# SpiderBackBackup.net
KiCad netlist of a schematic drawn in EAGLE
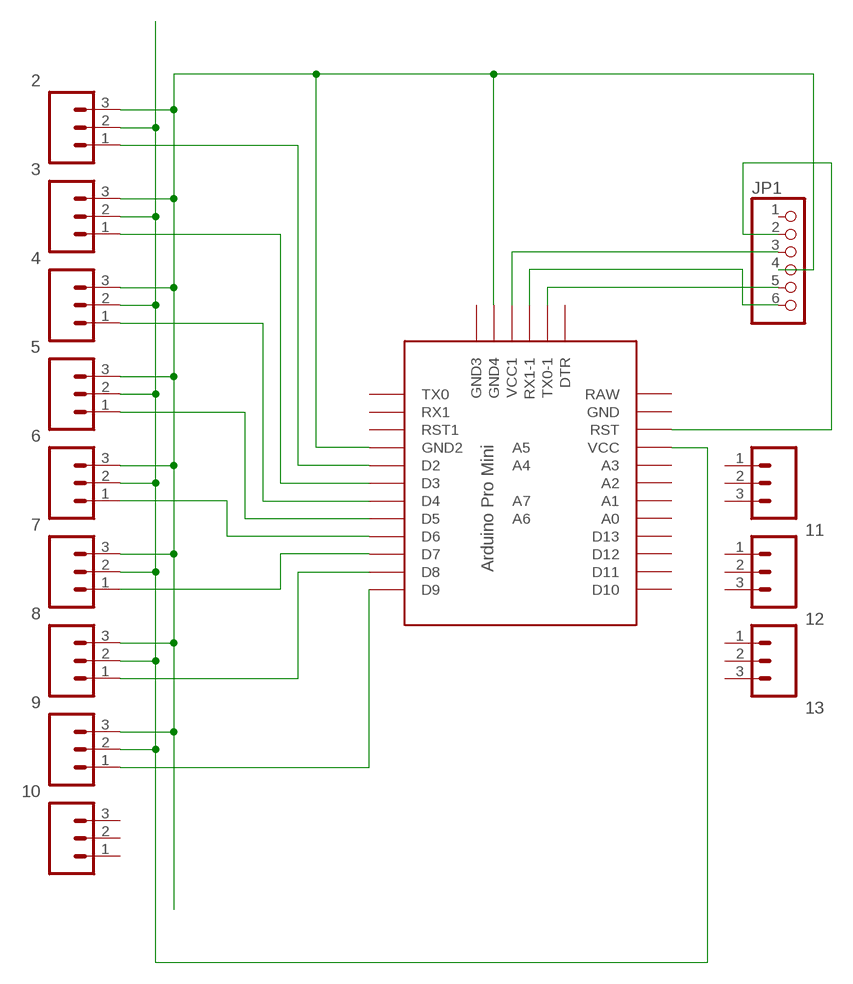
[diagram p0: schematic, sheet 1]

(export (version "E")
  (design (tool "Eeschema 10.0.6"))
  (components
    (comp (ref "2")
      (value "M03PTH")
      (footprint "eagle-import:1X03")
      (libsource (lib "eagle-import") (part "M03PTH"))
    )
    (comp (ref "3")
      (value "M03PTH")
      (footprint "eagle-import:1X03")
      (libsource (lib "eagle-import") (part "M03PTH"))
    )
    (comp (ref "4")
      (value "M03PTH")
      (footprint "eagle-import:1X03")
      (libsource (lib "eagle-import") (part "M03PTH"))
    )
    (comp (ref "5")
      (value "M03PTH")
      (footprint "eagle-import:1X03")
      (libsource (lib "eagle-import") (part "M03PTH"))
    )
    (comp (ref "6")
      (value "M03PTH")
      (footprint "eagle-import:1X03")
      (libsource (lib "eagle-import") (part "M03PTH"))
    )
    (comp (ref "7")
      (value "M03PTH")
      (footprint "eagle-import:1X03")
      (libsource (lib "eagle-import") (part "M03PTH"))
    )
    (comp (ref "8")
      (value "M03PTH")
      (footprint "eagle-import:1X03")
      (libsource (lib "eagle-import") (part "M03PTH"))
    )
    (comp (ref "9")
      (value "M03PTH")
      (footprint "eagle-import:1X03")
      (libsource (lib "eagle-import") (part "M03PTH"))
    )
    (comp (ref "10")
      (value "M03PTH")
      (footprint "eagle-import:1X03")
      (libsource (lib "eagle-import") (part "M03PTH"))
    )
    (comp (ref "11")
      (value "M03PTH")
      (footprint "eagle-import:1X03")
      (libsource (lib "eagle-import") (part "M03PTH"))
    )
    (comp (ref "12")
      (value "M03PTH")
      (footprint "eagle-import:1X03")
      (libsource (lib "eagle-import") (part "M03PTH"))
    )
    (comp (ref "13")
      (value "M03PTH")
      (footprint "eagle-import:1X03")
      (libsource (lib "eagle-import") (part "M03PTH"))
    )
    (comp (ref "JP1")
      (value "PINHD-1X6CB")
      (footprint "eagle-import:1X06-CLEANBIG")
      (libsource (lib "eagle-import") (part "PINHD-1X6CB"))
    )
    (comp (ref "U$1")
      (value "PRO-MINI-2")
      (footprint "eagle-import:PRO-MINI-2")
      (libsource (lib "eagle-import") (part "PRO-MINI-2"))
    )
  )
  (nets
    (net (code "1") (name "Net-(2-Pad1)") (class "Default")
      (node (ref "2") (pin "1") (pinfunction "1_1") (pintype "passive"))
      (node (ref "U$1") (pin "D2") (pinfunction "D2_D2") (pintype "bidirectional"))
    )
    (net (code "2") (name "Net-(2-Pad2)") (class "Default")
      (node (ref "2") (pin "2") (pinfunction "2_2") (pintype "passive"))
      (node (ref "3") (pin "2") (pinfunction "2_2") (pintype "passive"))
      (node (ref "4") (pin "2") (pinfunction "2_2") (pintype "passive"))
      (node (ref "5") (pin "2") (pinfunction "2_2") (pintype "passive"))
      (node (ref "6") (pin "2") (pinfunction "2_2") (pintype "passive"))
      (node (ref "7") (pin "2") (pinfunction "2_2") (pintype "passive"))
      (node (ref "8") (pin "2") (pinfunction "2_2") (pintype "passive"))
      (node (ref "9") (pin "2") (pinfunction "2_2") (pintype "passive"))
      (node (ref "U$1") (pin "VCC") (pinfunction "VCC_VCC") (pintype "bidirectional"))
    )
    (net (code "3") (name "Net-(3-Pad1)") (class "Default")
      (node (ref "3") (pin "1") (pinfunction "1_1") (pintype "passive"))
      (node (ref "U$1") (pin "D3") (pinfunction "D3_D3") (pintype "bidirectional"))
    )
    (net (code "4") (name "Net-(4-Pad1)") (class "Default")
      (node (ref "4") (pin "1") (pinfunction "1_1") (pintype "passive"))
      (node (ref "U$1") (pin "D4") (pinfunction "D4_D4") (pintype "bidirectional"))
    )
    (net (code "5") (name "Net-(5-Pad1)") (class "Default")
      (node (ref "5") (pin "1") (pinfunction "1_1") (pintype "passive"))
      (node (ref "U$1") (pin "D5") (pinfunction "D5_D5") (pintype "bidirectional"))
    )
    (net (code "6") (name "Net-(6-Pad1)") (class "Default")
      (node (ref "6") (pin "1") (pinfunction "1_1") (pintype "passive"))
      (node (ref "U$1") (pin "D6") (pinfunction "D6_D6") (pintype "bidirectional"))
    )
    (net (code "7") (name "Net-(7-Pad1)") (class "Default")
      (node (ref "7") (pin "1") (pinfunction "1_1") (pintype "passive"))
      (node (ref "U$1") (pin "D7") (pinfunction "D7_D7") (pintype "bidirectional"))
    )
    (net (code "8") (name "Net-(8-Pad1)") (class "Default")
      (node (ref "8") (pin "1") (pinfunction "1_1") (pintype "passive"))
      (node (ref "U$1") (pin "D8") (pinfunction "D8_D8") (pintype "bidirectional"))
    )
    (net (code "9") (name "Net-(9-Pad1)") (class "Default")
      (node (ref "9") (pin "1") (pinfunction "1_1") (pintype "passive"))
      (node (ref "U$1") (pin "D9") (pinfunction "D9_D9") (pintype "bidirectional"))
    )
    (net (code "10") (name "Net-(JP1-Pad2)") (class "Default")
      (node (ref "JP1") (pin "2") (pinfunction "2_2") (pintype "passive"))
      (node (ref "U$1") (pin "RST") (pinfunction "RST_RST") (pintype "bidirectional"))
    )
    (net (code "11") (name "Net-(JP1-Pad3)") (class "Default")
      (node (ref "JP1") (pin "3") (pinfunction "3_3") (pintype "passive"))
      (node (ref "U$1") (pin "VCC1") (pinfunction "VCC1_VCC1") (pintype "bidirectional"))
    )
    (net (code "12") (name "Net-(JP1-Pad5)") (class "Default")
      (node (ref "JP1") (pin "5") (pinfunction "5_5") (pintype "passive"))
      (node (ref "U$1") (pin "TX0-1") (pinfunction "TX0-1_TX0-1") (pintype "bidirectional"))
    )
    (net (code "13") (name "Net-(JP1-Pad6)") (class "Default")
      (node (ref "JP1") (pin "6") (pinfunction "6_6") (pintype "passive"))
      (node (ref "U$1") (pin "RX1-1") (pinfunction "RX1-1_RX1-1") (pintype "bidirectional"))
    )
    (net (code "14") (name "Net-(U$1-GND2)") (class "Default")
      (node (ref "2") (pin "3") (pinfunction "3_3") (pintype "passive"))
      (node (ref "3") (pin "3") (pinfunction "3_3") (pintype "passive"))
      (node (ref "4") (pin "3") (pinfunction "3_3") (pintype "passive"))
      (node (ref "5") (pin "3") (pinfunction "3_3") (pintype "passive"))
      (node (ref "6") (pin "3") (pinfunction "3_3") (pintype "passive"))
      (node (ref "7") (pin "3") (pinfunction "3_3") (pintype "passive"))
      (node (ref "8") (pin "3") (pinfunction "3_3") (pintype "passive"))
      (node (ref "9") (pin "3") (pinfunction "3_3") (pintype "passive"))
      (node (ref "JP1") (pin "4") (pinfunction "4_4") (pintype "passive"))
      (node (ref "U$1") (pin "GND1") (pinfunction "GND2_GND1") (pintype "bidirectional"))
      (node (ref "U$1") (pin "GND3") (pinfunction "GND4_GND3") (pintype "bidirectional"))
    )
    (net (code "15") (name "unconnected-(10-Pad1)") (class "Default")
      (node (ref "10") (pin "1") (pinfunction "1_1") (pintype "passive"))
    )
    (net (code "16") (name "unconnected-(10-Pad2)") (class "Default")
      (node (ref "10") (pin "2") (pinfunction "2_2") (pintype "passive"))
    )
    (net (code "17") (name "unconnected-(10-Pad3)") (class "Default")
      (node (ref "10") (pin "3") (pinfunction "3_3") (pintype "passive"))
    )
    (net (code "18") (name "unconnected-(11-Pad1)") (class "Default")
      (node (ref "11") (pin "1") (pinfunction "1_1") (pintype "passive"))
    )
    (net (code "19") (name "unconnected-(11-Pad2)") (class "Default")
      (node (ref "11") (pin "2") (pinfunction "2_2") (pintype "passive"))
    )
    (net (code "20") (name "unconnected-(11-Pad3)") (class "Default")
      (node (ref "11") (pin "3") (pinfunction "3_3") (pintype "passive"))
    )
    (net (code "21") (name "unconnected-(12-Pad1)") (class "Default")
      (node (ref "12") (pin "1") (pinfunction "1_1") (pintype "passive"))
    )
    (net (code "22") (name "unconnected-(12-Pad2)") (class "Default")
      (node (ref "12") (pin "2") (pinfunction "2_2") (pintype "passive"))
    )
    (net (code "23") (name "unconnected-(12-Pad3)") (class "Default")
      (node (ref "12") (pin "3") (pinfunction "3_3") (pintype "passive"))
    )
    (net (code "24") (name "unconnected-(13-Pad1)") (class "Default")
      (node (ref "13") (pin "1") (pinfunction "1_1") (pintype "passive"))
    )
    (net (code "25") (name "unconnected-(13-Pad2)") (class "Default")
      (node (ref "13") (pin "2") (pinfunction "2_2") (pintype "passive"))
    )
    (net (code "26") (name "unconnected-(13-Pad3)") (class "Default")
      (node (ref "13") (pin "3") (pinfunction "3_3") (pintype "passive"))
    )
    (net (code "27") (name "unconnected-(JP1-Pad1)") (class "Default")
      (node (ref "JP1") (pin "1") (pinfunction "1_1") (pintype "passive"))
    )
    (net (code "28") (name "unconnected-(U$1-GND3-PadGND2)") (class "Default")
      (node (ref "U$1") (pin "GND2") (pinfunction "GND3_GND2") (pintype "bidirectional"))
    )
    (net (code "29") (name "unconnected-(U$1-PadA0)") (class "Default")
      (node (ref "U$1") (pin "A0") (pinfunction "A0_A0") (pintype "bidirectional"))
    )
    (net (code "30") (name "unconnected-(U$1-PadA1)") (class "Default")
      (node (ref "U$1") (pin "A1") (pinfunction "A1_A1") (pintype "bidirectional"))
    )
    (net (code "31") (name "unconnected-(U$1-PadA2)") (class "Default")
      (node (ref "U$1") (pin "A2") (pinfunction "A2_A2") (pintype "bidirectional"))
    )
    (net (code "32") (name "unconnected-(U$1-PadA3)") (class "Default")
      (node (ref "U$1") (pin "A3") (pinfunction "A3_A3") (pintype "bidirectional"))
    )
    (net (code "33") (name "unconnected-(U$1-PadA4)") (class "Default")
      (node (ref "U$1") (pin "A4") (pinfunction "A4_A4") (pintype "bidirectional"))
    )
    (net (code "34") (name "unconnected-(U$1-PadA5)") (class "Default")
      (node (ref "U$1") (pin "A5") (pinfunction "A5_A5") (pintype "bidirectional"))
    )
    (net (code "35") (name "unconnected-(U$1-PadA6)") (class "Default")
      (node (ref "U$1") (pin "A6") (pinfunction "A6_A6") (pintype "bidirectional"))
    )
    (net (code "36") (name "unconnected-(U$1-PadA7)") (class "Default")
      (node (ref "U$1") (pin "A7") (pinfunction "A7_A7") (pintype "bidirectional"))
    )
    (net (code "37") (name "unconnected-(U$1-PadD10)") (class "Default")
      (node (ref "U$1") (pin "D10") (pinfunction "D10_D10") (pintype "bidirectional"))
    )
    (net (code "38") (name "unconnected-(U$1-PadD11)") (class "Default")
      (node (ref "U$1") (pin "D11") (pinfunction "D11_D11") (pintype "bidirectional"))
    )
    (net (code "39") (name "unconnected-(U$1-PadD12)") (class "Default")
      (node (ref "U$1") (pin "D12") (pinfunction "D12_D12") (pintype "bidirectional"))
    )
    (net (code "40") (name "unconnected-(U$1-PadD13)") (class "Default")
      (node (ref "U$1") (pin "D13") (pinfunction "D13_D13") (pintype "bidirectional"))
    )
    (net (code "41") (name "unconnected-(U$1-PadDTR)") (class "Default")
      (node (ref "U$1") (pin "DTR") (pinfunction "DTR_DTR") (pintype "bidirectional"))
    )
    (net (code "42") (name "unconnected-(U$1-PadGND)") (class "Default")
      (node (ref "U$1") (pin "GND") (pinfunction "GND_GND") (pintype "bidirectional"))
    )
    (net (code "43") (name "unconnected-(U$1-PadRAW)") (class "Default")
      (node (ref "U$1") (pin "RAW") (pinfunction "RAW_RAW") (pintype "bidirectional"))
    )
    (net (code "44") (name "unconnected-(U$1-PadRST1)") (class "Default")
      (node (ref "U$1") (pin "RST1") (pinfunction "RST1_RST1") (pintype "bidirectional"))
    )
    (net (code "45") (name "unconnected-(U$1-PadRX1)") (class "Default")
      (node (ref "U$1") (pin "RX1") (pinfunction "RX1_RX1") (pintype "bidirectional"))
    )
    (net (code "46") (name "unconnected-(U$1-PadTX0)") (class "Default")
      (node (ref "U$1") (pin "TX0") (pinfunction "TX0_TX0") (pintype "bidirectional"))
    )
  )
)
